# PX4FLOW2_1_Sensors_CAN_X0.net
KiCad netlist of a schematic drawn in Altium Designer
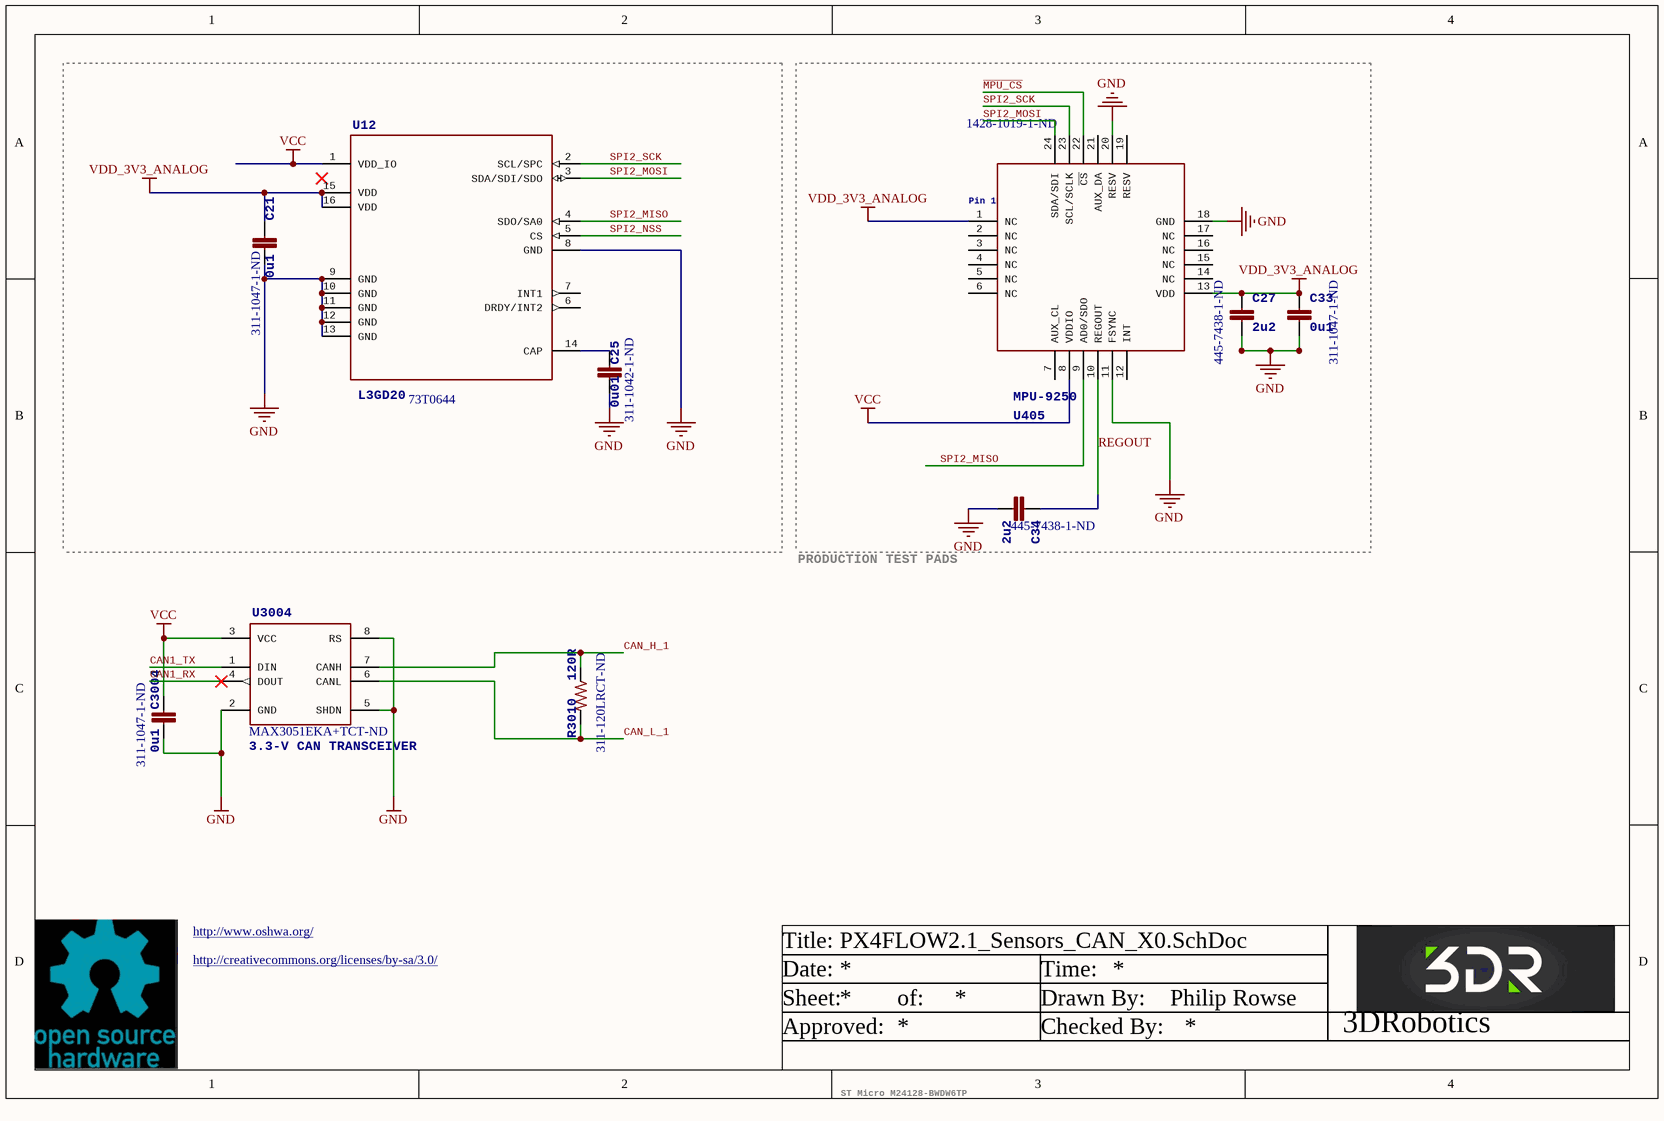
[diagram p0: PX4FLOW2.1_Sensors_CAN_X0.SchDoc]

(export (version "E")
  (design (tool "Eeschema 10.0.6"))
  (components
    (comp (ref "C21")
      (value "0u1")
      (footprint "C0402")
      (description "CapacitorStandard 0603 ceramic capacitor, and 0.1\" leaded capacitor.")
      (fields
        (field (name "PARTNO") "CC0402ZRY5V7BB104")
        (field (name "SUPPLIER PART NUMBER 1") "311-1047-1-ND")
      )
      (libsource (lib "pixhawk2") (part "CAP0402-CAP"))
    )
    (comp (ref "C25")
      (value "0u01")
      (footprint "C0402")
      (description "CapacitorStandard 0603 ceramic capacitor, and 0.1\" leaded capacitor.")
      (fields
        (field (name "PARTNO") "CC0402KRX7R7BB103")
        (field (name "SUPPLIER PART NUMBER 1") "311-1042-1-ND")
      )
      (libsource (lib "pixhawk2") (part "CAP0402-CAP"))
    )
    (comp (ref "C27")
      (value "2u2")
      (footprint "0603-CAP")
      (description "Capacitor, 2.2uF, 16V, 10%, X6S, 0603, Ceramic")
      (fields
        (field (name "PARTNO") "C1608X6S1C225K080AC")
        (field (name "SUPPLIER PART NUMBER 1") "445-7438-1-ND")
        (field (name "3DR_PARTNO") "ECM0619")
      )
      (libsource (lib "") (part "CAPACITOR-0603_1"))
    )
    (comp (ref "C33")
      (value "0u1")
      (footprint "0402-CAP")
      (description "Capacitor, 0.1uF, 16V, Y5V, 0402, Ceramic")
      (fields
        (field (name "PARTNO") "CC0402ZRY5V7BB104")
        (field (name "SUPPLIER PART NUMBER 1") "311-1047-1-ND")
        (field (name "3DR_PARTNO") "ECM0700")
      )
      (libsource (lib "lib_pixhawk") (part "CAPACITOR-0402"))
    )
    (comp (ref "C34")
      (value "2u2")
      (footprint "0603-CAP")
      (description "Capacitor, 2.2uF, 16V, 10%, X6S, 0603, Ceramic")
      (fields
        (field (name "PARTNO") "C1608X6S1C225K080AC")
        (field (name "SUPPLIER PART NUMBER 1") "445-7438-1-ND")
        (field (name "3DR_PARTNO") "ECM0619")
      )
      (libsource (lib "lib_pixhawk") (part "CAPACITOR-0603"))
    )
    (comp (ref "C3004")
      (value "0u1")
      (footprint "0402-CAP")
      (description "CAP CER 0.1UF 16V Y5V 0402")
      (fields
        (field (name "PARTNO") "CC0402ZRY5V7BB104")
        (field (name "SUPPLIER PART NUMBER 1") "311-1047-1-ND")
        (field (name "3DR_PARTNO") "ECM0700")
      )
      (libsource (lib "pixhawk2") (part "CAP0402"))
    )
    (comp (ref "R3010")
      (value "120R")
      (footprint "R0402")
      (description "RES 120 OHM 1/16W 1% 0402 SMD")
      (fields
        (field (name "PARTNO") "RC0402FR-07120RL")
        (field (name "SUPPLIER PART NUMBER 1") "311-120LRCT-ND")
        (field (name "3DR_PARTNO") "ECM0820")
      )
      (libsource (lib "pixhawk2") (part "RESISTOR0402-RES"))
    )
    (comp (ref "U12")
      (value "L3GD20")
      (footprint "L3GD20")
      (description "Sensor, Low-power, Three-axis, Angular rate")
      (fields (field (name "SUPPLIER PART NUMBER 1") "73T0644") (field (name "3DR_PARTNO") "ECM0827"))
      (libsource (lib "pixhawk2") (part "L3GD20"))
    )
    (comp (ref "U405")
      (value "MPU-9250")
      (footprint "MPU-6500")
      (fields (field (name "PIN 1") "Pin 1") (field (name "SUPPLIER PART NUMBER 1") "1428-1019-1-ND"))
      (libsource (lib "pixhawk2") (part "MPU-6500"))
    )
    (comp (ref "U3004")
      (value "3.3-V CAN TRANSCEIVER")
      (footprint "SOT23-8")
      (description "IC TXRX CAN 1MBPS SOT23-8")
      (fields
        (field (name "SUPPLIER PART NUMBER 1") "MAX3051EKA+TCT-ND")
        (field (name "3DR_PARTNO") "ECM0831")
        (field (name "PARTNO") "MAX3051EKA+T")
      )
      (libsource (lib "pixhawk2") (part "MAX3051MAX3051EKA"))
    )
  )
  (nets
    (net (code "1") (name "/CAN1_RX") (class "Default")
      (node (ref "U3004") (pin "4") (pinfunction "DOUT_4") (pintype "output+no_connect"))
    )
    (net (code "2") (name "/CAN1_TX") (class "Default")
      (node (ref "U3004") (pin "1") (pinfunction "DIN_1") (pintype "passive"))
    )
    (net (code "3") (name "/CAN_H_1") (class "Default")
      (node (ref "R3010") (pin "1") (pinfunction "1_1") (pintype "passive"))
      (node (ref "U3004") (pin "7") (pinfunction "CANH_7") (pintype "passive"))
    )
    (net (code "4") (name "/CAN_L_1") (class "Default")
      (node (ref "R3010") (pin "2") (pinfunction "2_2") (pintype "passive"))
      (node (ref "U3004") (pin "6") (pinfunction "CANL_6") (pintype "passive"))
    )
    (net (code "5") (name "/REGOUT") (class "Default")
      (node (ref "C34") (pin "P$1") (pinfunction "1_P$1") (pintype "passive"))
      (node (ref "U405") (pin "10") (pinfunction "REGOUT_10") (pintype "passive"))
    )
    (net (code "6") (name "/SPI2_MISO") (class "Default")
      (node (ref "U12") (pin "4") (pinfunction "SDO/SA0_4") (pintype "input"))
      (node (ref "U405") (pin "9") (pinfunction "AD0/SDO_9") (pintype "passive"))
    )
    (net (code "7") (name "/SPI2_MOSI") (class "Default")
      (node (ref "U12") (pin "3") (pinfunction "SDA/SDI/SDO_3") (pintype "bidirectional"))
      (node (ref "U405") (pin "24") (pinfunction "SDA/SDI_24") (pintype "passive"))
    )
    (net (code "8") (name "/SPI2_NSS") (class "Default")
      (node (ref "U12") (pin "5") (pinfunction "CS_5") (pintype "input"))
    )
    (net (code "9") (name "/SPI2_SCK") (class "Default")
      (node (ref "U12") (pin "2") (pinfunction "SCL/SPC_2") (pintype "input"))
      (node (ref "U405") (pin "23") (pinfunction "SCL/SCLK_23") (pintype "passive"))
    )
    (net (code "10") (name "/~{MPU_CS}") (class "Default")
      (node (ref "U405") (pin "22") (pinfunction "~{CS}_22") (pintype "passive"))
    )
    (net (code "11") (name "GND") (class "Default")
      (node (ref "C21") (pin "2") (pinfunction "2_2") (pintype "passive"))
      (node (ref "C25") (pin "2") (pinfunction "2_2") (pintype "passive"))
      (node (ref "C27") (pin "P$2") (pinfunction "2_P$2") (pintype "passive"))
      (node (ref "C3004") (pin "P$2") (pinfunction "2_P$2") (pintype "passive"))
      (node (ref "C33") (pin "P$2") (pinfunction "2_P$2") (pintype "passive"))
      (node (ref "C34") (pin "P$2") (pinfunction "2_P$2") (pintype "passive"))
      (node (ref "U12") (pin "10") (pinfunction "GND_10") (pintype "power_in"))
      (node (ref "U12") (pin "11") (pinfunction "GND_11") (pintype "power_in"))
      (node (ref "U12") (pin "12") (pinfunction "GND_12") (pintype "power_in"))
      (node (ref "U12") (pin "13") (pinfunction "GND_13") (pintype "power_in"))
      (node (ref "U12") (pin "8") (pinfunction "GND_8") (pintype "power_in"))
      (node (ref "U12") (pin "9") (pinfunction "GND_9") (pintype "power_in"))
      (node (ref "U3004") (pin "2") (pinfunction "GND_2") (pintype "power_in"))
      (node (ref "U3004") (pin "5") (pinfunction "SHDN_5") (pintype "passive"))
      (node (ref "U3004") (pin "8") (pinfunction "RS_8") (pintype "passive"))
      (node (ref "U405") (pin "11") (pinfunction "FSYNC_11") (pintype "passive"))
      (node (ref "U405") (pin "18") (pinfunction "GND_18") (pintype "passive"))
      (node (ref "U405") (pin "20") (pinfunction "RESV_20") (pintype "passive"))
    )
    (net (code "12") (name "Net-(U12-CAP)") (class "Default")
      (node (ref "C25") (pin "1") (pinfunction "1_1") (pintype "passive"))
      (node (ref "U12") (pin "14") (pinfunction "CAP_14") (pintype "passive"))
    )
    (net (code "13") (name "VCC") (class "Default")
      (node (ref "C3004") (pin "P$1") (pinfunction "1_P$1") (pintype "passive"))
      (node (ref "U12") (pin "1") (pinfunction "VDD_IO_1") (pintype "power_in"))
      (node (ref "U3004") (pin "3") (pinfunction "VCC_3") (pintype "passive"))
      (node (ref "U405") (pin "8") (pinfunction "VDDIO_8") (pintype "passive"))
    )
    (net (code "14") (name "VDD_3V3_ANALOG") (class "Default")
      (node (ref "C21") (pin "1") (pinfunction "1_1") (pintype "passive"))
      (node (ref "C27") (pin "P$1") (pinfunction "1_P$1") (pintype "passive"))
      (node (ref "C33") (pin "P$1") (pinfunction "1_P$1") (pintype "passive"))
      (node (ref "U12") (pin "15") (pinfunction "VDD_15") (pintype "power_in"))
      (node (ref "U12") (pin "16") (pinfunction "VDD_16") (pintype "power_in"))
      (node (ref "U405") (pin "1") (pinfunction "NC_1") (pintype "passive"))
      (node (ref "U405") (pin "13") (pinfunction "VDD_13") (pintype "passive"))
    )
    (net (code "15") (name "unconnected-(U12-DRDY{slash}INT2-Pad6)") (class "Default")
      (node (ref "U12") (pin "6") (pinfunction "DRDY/INT2_6") (pintype "output"))
    )
    (net (code "16") (name "unconnected-(U12-INT1-Pad7)") (class "Default")
      (node (ref "U12") (pin "7") (pinfunction "INT1_7") (pintype "output"))
    )
    (net (code "17") (name "unconnected-(U405-AUX_CL-Pad7)") (class "Default")
      (node (ref "U405") (pin "7") (pinfunction "AUX_CL_7") (pintype "passive"))
    )
    (net (code "18") (name "unconnected-(U405-AUX_DA-Pad21)") (class "Default")
      (node (ref "U405") (pin "21") (pinfunction "AUX_DA_21") (pintype "passive"))
    )
    (net (code "19") (name "unconnected-(U405-INT-Pad12)") (class "Default")
      (node (ref "U405") (pin "12") (pinfunction "INT_12") (pintype "passive"))
    )
    (net (code "20") (name "unconnected-(U405-NC-Pad2)") (class "Default")
      (node (ref "U405") (pin "2") (pinfunction "NC_2") (pintype "passive"))
    )
    (net (code "21") (name "unconnected-(U405-NC-Pad3)") (class "Default")
      (node (ref "U405") (pin "3") (pinfunction "NC_3") (pintype "passive"))
    )
    (net (code "22") (name "unconnected-(U405-NC-Pad4)") (class "Default")
      (node (ref "U405") (pin "4") (pinfunction "NC_4") (pintype "passive"))
    )
    (net (code "23") (name "unconnected-(U405-NC-Pad5)") (class "Default")
      (node (ref "U405") (pin "5") (pinfunction "NC_5") (pintype "passive"))
    )
    (net (code "24") (name "unconnected-(U405-NC-Pad6)") (class "Default")
      (node (ref "U405") (pin "6") (pinfunction "NC_6") (pintype "passive"))
    )
    (net (code "25") (name "unconnected-(U405-NC-Pad14)") (class "Default")
      (node (ref "U405") (pin "14") (pinfunction "NC_14") (pintype "passive"))
    )
    (net (code "26") (name "unconnected-(U405-NC-Pad15)") (class "Default")
      (node (ref "U405") (pin "15") (pinfunction "NC_15") (pintype "passive"))
    )
    (net (code "27") (name "unconnected-(U405-NC-Pad16)") (class "Default")
      (node (ref "U405") (pin "16") (pinfunction "NC_16") (pintype "passive"))
    )
    (net (code "28") (name "unconnected-(U405-NC-Pad17)") (class "Default")
      (node (ref "U405") (pin "17") (pinfunction "NC_17") (pintype "passive"))
    )
    (net (code "29") (name "unconnected-(U405-RESV-Pad19)") (class "Default")
      (node (ref "U405") (pin "19") (pinfunction "RESV_19") (pintype "passive"))
    )
  )
)
